# Sheet2.net
KiCad netlist of a schematic drawn in Altium Designer
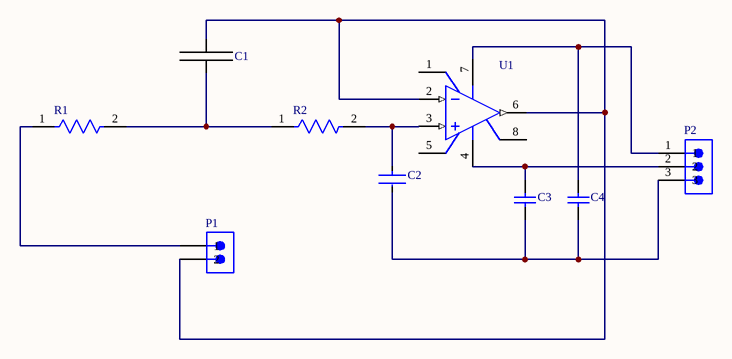
[diagram p0: Sheet2.SchDoc]

(export (version "E")
  (design (tool "Eeschema 10.0.6"))
  (components
    (comp (ref "C1") (value "Cap_0805") (footprint "C_0805") (libsource (lib "Cap") (part "Cap_0805")))
    (comp (ref "C2")
      (value "C0402C152K5RACTU")
      (footprint "FP-C0402-BB-MFG")
      (description "CAP CER 1500PF 50V X7R 0402")
      (fields
        (field (name "OCTOPART") "https://octopart.com/c0402c152k5ractu-kemet-125298")
        (field (name "TOLERANCE") "0.1")
      )
      (libsource (lib "Altium Content Vault") (part "b4654b650e69147ec39a6b967a45e02"))
    )
    (comp (ref "C3")
      (value "1206GC102KAT1A")
      (footprint "AVX-1206-2_L")
      (description "Chip Capacitor, 1 nF, +/- 10%, -55 to 125 degC, 1206 (3216 Metric), RoHS, Tape and Reel")
      (fields (field (name "TOLERANCE") "10%") (field (name "MANUFACTURER") "AVX"))
      (libsource (lib "Altium Content Vault") (part "CAP-NP-2"))
    )
    (comp (ref "C4")
      (value "1206GC102KAT1A")
      (footprint "AVX-1206-2_L")
      (description "Chip Capacitor, 1 nF, +/- 10%, -55 to 125 degC, 1206 (3216 Metric), RoHS, Tape and Reel")
      (fields (field (name "TOLERANCE") "10%") (field (name "MANUFACTURER") "AVX"))
      (libsource (lib "Altium Content Vault") (part "CAP-NP-2"))
    )
    (comp (ref "P1")
      (value "691701510002B")
      (footprint "691701510002B")
      (libsource (lib "Altium Content Vault") (part "TBL - 1R - 02P - Male"))
    )
    (comp (ref "P2")
      (value "620303124022")
      (footprint "620303124022")
      (libsource (lib "Altium Content Vault") (part "Header_Male_1R_03P"))
    )
    (comp (ref "R1")
      (value "RG1005P-393-B-T5")
      (footprint "FP-RG1005-IPC_B")
      (description "Automotive Metal Thin Film Chip Resistor, 0402, 39kΩ, 0.1%, 25ppm/°C, 0.0625W, 75V")
      (fields (field (name "TOLERANCE") "0.1%"))
      (libsource (lib "Altium Content Vault") (part "1029c3af85768c4190bb7ad29bc67b5"))
    )
    (comp (ref "R2")
      (value "RG1005P-393-B-T5")
      (footprint "FP-RG1005-IPC_B")
      (description "Automotive Metal Thin Film Chip Resistor, 0402, 39kΩ, 0.1%, 25ppm/°C, 0.0625W, 75V")
      (fields (field (name "TOLERANCE") "0.1%"))
      (libsource (lib "Altium Content Vault") (part "1029c3af85768c4190bb7ad29bc67b5"))
    )
    (comp (ref "U1")
      (value "LM741H")
      (footprint "LMC0008A")
      (description "Operational Amplifier, 8-pin TO-99")
      (fields (field (name "MANUFACTURER") "Texas Instruments"))
      (libsource (lib "Altium Content Vault") (part "AMP-OPA-LM741-8"))
    )
  )
  (nets
    (net (code "1") (name "Net-(C1-Pad1)") (class "Default")
      (node (ref "C1") (pin "1") (pinfunction "1_1") (pintype "passive"))
      (node (ref "R1") (pin "2") (pinfunction "2_2") (pintype "passive"))
      (node (ref "R2") (pin "1") (pinfunction "1_1") (pintype "passive"))
    )
    (net (code "2") (name "Net-(C2-Pad2)") (class "Default")
      (node (ref "C2") (pin "2") (pinfunction "2_2") (pintype "passive"))
      (node (ref "C3") (pin "1") (pinfunction "1_1") (pintype "passive"))
      (node (ref "C4") (pin "1") (pinfunction "1_1") (pintype "passive"))
      (node (ref "P2") (pin "3") (pinfunction "3_3") (pintype "passive"))
    )
    (net (code "3") (name "Net-(P1-Pad1)") (class "Default")
      (node (ref "P1") (pin "1") (pinfunction "1_1") (pintype "passive"))
      (node (ref "R1") (pin "1") (pinfunction "1_1") (pintype "passive"))
    )
    (net (code "4") (name "Net-(U1-IN+)") (class "Default")
      (node (ref "C2") (pin "1") (pinfunction "1_1") (pintype "passive"))
      (node (ref "R2") (pin "2") (pinfunction "2_2") (pintype "passive"))
      (node (ref "U1") (pin "3") (pinfunction "IN+_3") (pintype "input"))
    )
    (net (code "5") (name "Net-(U1-IN-)") (class "Default")
      (node (ref "C1") (pin "2") (pinfunction "2_2") (pintype "passive"))
      (node (ref "P1") (pin "2") (pinfunction "2_2") (pintype "passive"))
      (node (ref "U1") (pin "2") (pinfunction "IN-_2") (pintype "input"))
      (node (ref "U1") (pin "6") (pinfunction "OUT_6") (pintype "output"))
    )
    (net (code "6") (name "Net-(U1-V+)") (class "Default")
      (node (ref "C4") (pin "2") (pinfunction "2_2") (pintype "passive"))
      (node (ref "P2") (pin "1") (pinfunction "1_1") (pintype "passive"))
      (node (ref "U1") (pin "7") (pinfunction "V+_7") (pintype "power_in"))
    )
    (net (code "7") (name "Net-(U1-V-)") (class "Default")
      (node (ref "C3") (pin "2") (pinfunction "2_2") (pintype "passive"))
      (node (ref "P2") (pin "2") (pinfunction "2_2") (pintype "passive"))
      (node (ref "U1") (pin "4") (pinfunction "V-_4") (pintype "power_in"))
    )
    (net (code "8") (name "unconnected-(U1-NC-Pad8)") (class "Default")
      (node (ref "U1") (pin "8") (pinfunction "NC_8") (pintype "passive"))
    )
    (net (code "9") (name "unconnected-(U1-OFS_NULL-Pad1)") (class "Default")
      (node (ref "U1") (pin "1") (pinfunction "OFS_NULL_1") (pintype "passive"))
    )
    (net (code "10") (name "unconnected-(U1-OFS_NULL-Pad5)") (class "Default")
      (node (ref "U1") (pin "5") (pinfunction "OFS_NULL_5") (pintype "passive"))
    )
  )
)
